# Interactive_SparkFun_Badge.net
KiCad netlist of a schematic drawn in EAGLE
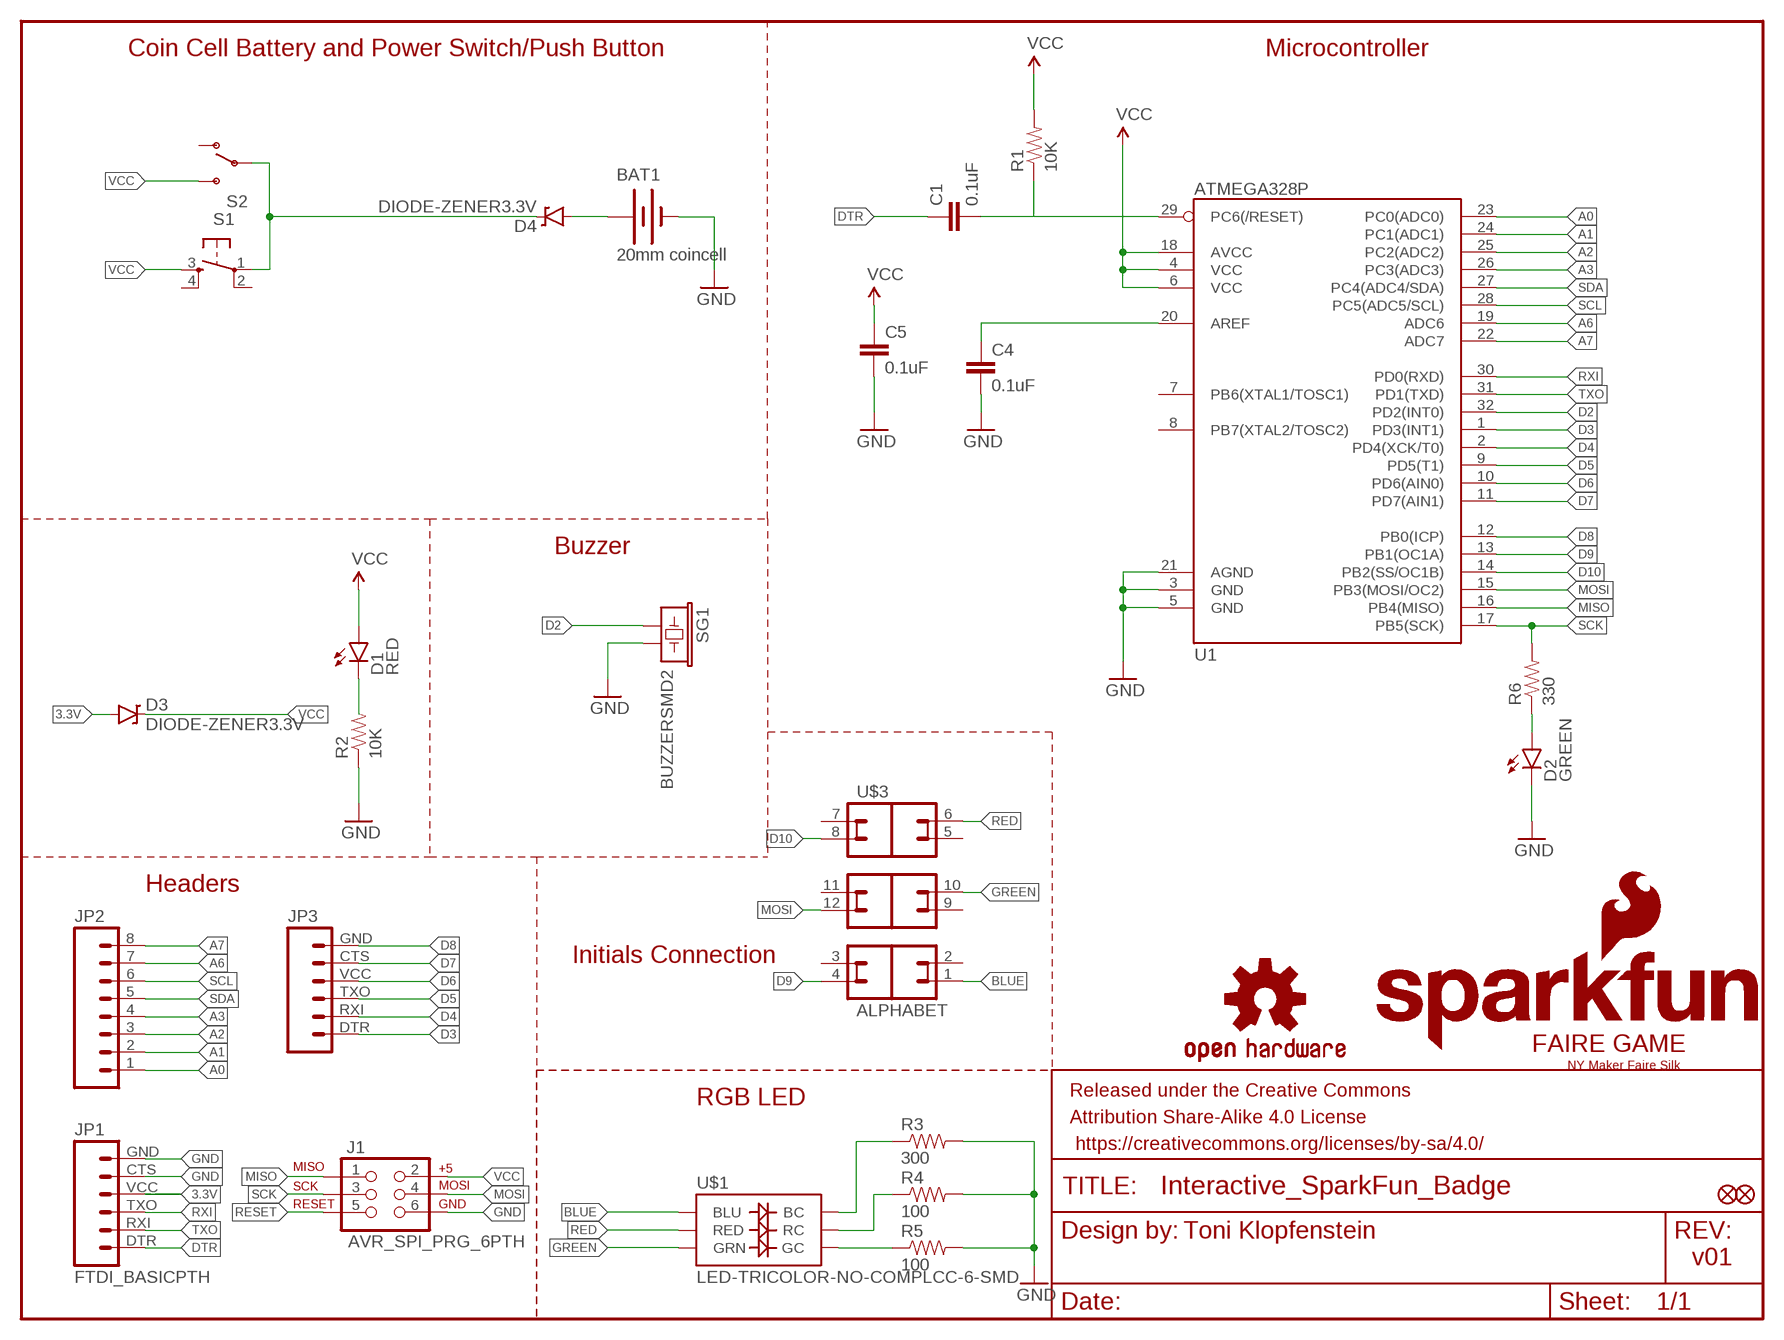
[diagram p0: schematic, sheet 1]

(export (version "E")
  (design (tool "Eeschema 10.0.6"))
  (components
    (comp (ref "BAT1")
      (value "20mm coincell")
      (footprint "eagle-import:BATTCON_20MM_4LEGS")
      (libsource (lib "eagle-import") (part "BATTERY20MM_4LEGS"))
    )
    (comp (ref "C1")
      (value "0.1uF")
      (footprint "eagle-import:0603-CAP")
      (libsource (lib "eagle-import") (part "0.1UF-25V(+80/-20%)(0603)"))
    )
    (comp (ref "C4")
      (value "0.1uF")
      (footprint "eagle-import:0603-CAP")
      (libsource (lib "eagle-import") (part "0.1UF-25V(+80/-20%)(0603)"))
    )
    (comp (ref "C5")
      (value "0.1uF")
      (footprint "eagle-import:0603-CAP")
      (libsource (lib "eagle-import") (part "0.1UF-25V(+80/-20%)(0603)"))
    )
    (comp (ref "D1")
      (value "RED")
      (footprint "eagle-import:LED-0603")
      (libsource (lib "eagle-import") (part "LED-RED0603"))
    )
    (comp (ref "D2")
      (value "GREEN")
      (footprint "eagle-import:LED-0603")
      (libsource (lib "eagle-import") (part "LED-GREEN0603"))
    )
    (comp (ref "D3")
      (value "DIODE-ZENER3.3V")
      (footprint "eagle-import:SOD-323")
      (libsource (lib "eagle-import") (part "DIODE-ZENER3.3V"))
    )
    (comp (ref "D4")
      (value "DIODE-ZENER3.3V")
      (footprint "eagle-import:SOD-323")
      (libsource (lib "eagle-import") (part "DIODE-ZENER3.3V"))
    )
    (comp (ref "FID1")
      (value "FIDUCIAL1X2")
      (footprint "eagle-import:FIDUCIAL-1X2")
      (libsource (lib "eagle-import") (part "FIDUCIAL1X2"))
    )
    (comp (ref "FID2")
      (value "FIDUCIAL1X2")
      (footprint "eagle-import:FIDUCIAL-1X2")
      (libsource (lib "eagle-import") (part "FIDUCIAL1X2"))
    )
    (comp (ref "FRAME1")
      (value "FRAME-LETTER")
      (footprint "eagle-import:CREATIVE_COMMONS")
      (libsource (lib "eagle-import") (part "FRAME-LETTER"))
    )
    (comp (ref "J1")
      (value "AVR_SPI_PRG_6PTH")
      (footprint "eagle-import:2X3")
      (libsource (lib "eagle-import") (part "AVR_SPI_PRG_6PTH"))
    )
    (comp (ref "JP1")
      (value "FTDI_BASICPTH")
      (footprint "eagle-import:FTDI_BASIC")
      (libsource (lib "eagle-import") (part "FTDI_BASICPTH"))
    )
    (comp (ref "JP2")
      (value "M081X08")
      (footprint "eagle-import:1X08")
      (libsource (lib "eagle-import") (part "M081X08"))
    )
    (comp (ref "JP3")
      (value "M06SIP")
      (footprint "eagle-import:1X06")
      (libsource (lib "eagle-import") (part "M06SIP"))
    )
    (comp (ref "LOGO1")
      (value "OSHW-LOGOM")
      (footprint "eagle-import:OSHW-LOGO-M")
      (libsource (lib "eagle-import") (part "OSHW-LOGOM"))
    )
    (comp (ref "R1")
      (value "10K")
      (footprint "eagle-import:0603-RES")
      (libsource (lib "eagle-import") (part "10KOHM1/10W1%(0603)0603"))
    )
    (comp (ref "R2")
      (value "10K")
      (footprint "eagle-import:0603-RES")
      (libsource (lib "eagle-import") (part "10KOHM1/10W1%(0603)0603"))
    )
    (comp (ref "R3")
      (value "300")
      (footprint "eagle-import:0603-RES")
      (libsource (lib "eagle-import") (part "300OHM-1/10W-1%(0603)"))
    )
    (comp (ref "R4")
      (value "100")
      (footprint "eagle-import:0603-RES")
      (libsource (lib "eagle-import") (part "100OHM1/10W1%(0603)"))
    )
    (comp (ref "R5")
      (value "100")
      (footprint "eagle-import:0603-RES")
      (libsource (lib "eagle-import") (part "100OHM1/10W1%(0603)"))
    )
    (comp (ref "R6")
      (value "330")
      (footprint "eagle-import:0603-RES")
      (libsource (lib "eagle-import") (part "330OHM1/10W1%(0603)"))
    )
    (comp (ref "S1")
      (value "TAC_SWITCHSMD")
      (footprint "eagle-import:TACTILE-SWITCH-SMD")
      (libsource (lib "eagle-import") (part "TAC_SWITCHSMD"))
    )
    (comp (ref "S2")
      (value "SWITCH-SPDTSMD")
      (footprint "eagle-import:AYZ0202")
      (libsource (lib "eagle-import") (part "SWITCH-SPDTSMD"))
    )
    (comp (ref "SG1")
      (value "BUZZERSMD2")
      (footprint "eagle-import:BUZZER-CCV")
      (libsource (lib "eagle-import") (part "BUZZERSMD2"))
    )
    (comp (ref "U$1")
      (value "LED-TRICOLOR-NO-COMPLCC-6-SMD")
      (footprint "eagle-import:PLCC-6-LED")
      (libsource (lib "eagle-import") (part "LED-TRICOLOR-NO-COMPLCC-6-SMD"))
    )
    (comp (ref "U$2")
      (value "NY_FAIRE_BACK")
      (footprint "eagle-import:NY_BACK")
      (libsource (lib "eagle-import") (part "NY_FAIRE_BACK"))
    )
    (comp (ref "U$3")
      (value "ALPHABET")
      (footprint "eagle-import:INITIALS")
      (libsource (lib "eagle-import") (part "ALPHABET"))
    )
    (comp (ref "U$4")
      (value "FAIRE_GAME_SILK")
      (footprint "eagle-import:FAIRE_GAME_SILK")
      (libsource (lib "eagle-import") (part "FAIRE_GAME_SILK"))
    )
    (comp (ref "U1")
      (value "ATMEGA328P")
      (footprint "eagle-import:TQFP32-08")
      (libsource (lib "eagle-import") (part "ATMEGA328_SMT"))
    )
  )
  (nets
    (net (code "1") (name "3.3V") (class "Default")
      (node (ref "D3") (pin "A") (pinfunction "A_A") (pintype "passive"))
      (node (ref "JP1") (pin "VCC") (pinfunction "4_VCC") (pintype "passive"))
    )
    (net (code "2") (name "A0") (class "Default")
      (node (ref "JP2") (pin "1") (pinfunction "1_1") (pintype "passive"))
      (node (ref "U1") (pin "23") (pinfunction "PC0(ADC0)_23") (pintype "bidirectional"))
    )
    (net (code "3") (name "A1") (class "Default")
      (node (ref "JP2") (pin "2") (pinfunction "2_2") (pintype "passive"))
      (node (ref "U1") (pin "24") (pinfunction "PC1(ADC1)_24") (pintype "bidirectional"))
    )
    (net (code "4") (name "A2") (class "Default")
      (node (ref "JP2") (pin "3") (pinfunction "3_3") (pintype "passive"))
      (node (ref "U1") (pin "25") (pinfunction "PC2(ADC2)_25") (pintype "bidirectional"))
    )
    (net (code "5") (name "A3") (class "Default")
      (node (ref "JP2") (pin "4") (pinfunction "4_4") (pintype "passive"))
      (node (ref "U1") (pin "26") (pinfunction "PC3(ADC3)_26") (pintype "bidirectional"))
    )
    (net (code "6") (name "A6") (class "Default")
      (node (ref "JP2") (pin "7") (pinfunction "7_7") (pintype "passive"))
      (node (ref "U1") (pin "19") (pinfunction "ADC6_19") (pintype "bidirectional"))
    )
    (net (code "7") (name "A7") (class "Default")
      (node (ref "JP2") (pin "8") (pinfunction "8_8") (pintype "passive"))
      (node (ref "U1") (pin "22") (pinfunction "ADC7_22") (pintype "bidirectional"))
    )
    (net (code "8") (name "BLUE") (class "Default")
      (node (ref "U$1") (pin "AB") (pinfunction "BLU_AB") (pintype "bidirectional"))
      (node (ref "U$3") (pin "1") (pinfunction "1_1") (pintype "passive"))
    )
    (net (code "9") (name "D2") (class "Default")
      (node (ref "SG1") (pin "+") (pinfunction "1_+") (pintype "passive"))
      (node (ref "U1") (pin "32") (pinfunction "PD2(INT0)_32") (pintype "bidirectional"))
    )
    (net (code "10") (name "D3") (class "Default")
      (node (ref "JP3") (pin "DTR") (pinfunction "1_DTR") (pintype "passive"))
      (node (ref "U1") (pin "1") (pinfunction "PD3(INT1)_1") (pintype "bidirectional"))
    )
    (net (code "11") (name "D4") (class "Default")
      (node (ref "JP3") (pin "RXI") (pinfunction "2_RXI") (pintype "passive"))
      (node (ref "U1") (pin "2") (pinfunction "PD4(XCK/T0)_2") (pintype "bidirectional"))
    )
    (net (code "12") (name "D5") (class "Default")
      (node (ref "JP3") (pin "TXO") (pinfunction "3_TXO") (pintype "passive"))
      (node (ref "U1") (pin "9") (pinfunction "PD5(T1)_9") (pintype "bidirectional"))
    )
    (net (code "13") (name "D6") (class "Default")
      (node (ref "JP3") (pin "VCC") (pinfunction "4_VCC") (pintype "passive"))
      (node (ref "U1") (pin "10") (pinfunction "PD6(AIN0)_10") (pintype "bidirectional"))
    )
    (net (code "14") (name "D7") (class "Default")
      (node (ref "JP3") (pin "CTS") (pinfunction "5_CTS") (pintype "passive"))
      (node (ref "U1") (pin "11") (pinfunction "PD7(AIN1)_11") (pintype "bidirectional"))
    )
    (net (code "15") (name "D8") (class "Default")
      (node (ref "JP3") (pin "GND") (pinfunction "6_GND") (pintype "passive"))
      (node (ref "U1") (pin "12") (pinfunction "PB0(ICP)_12") (pintype "bidirectional"))
    )
    (net (code "16") (name "D9") (class "Default")
      (node (ref "U$3") (pin "4") (pinfunction "4_4") (pintype "passive"))
      (node (ref "U1") (pin "13") (pinfunction "PB1(OC1A)_13") (pintype "bidirectional"))
    )
    (net (code "17") (name "D10") (class "Default")
      (node (ref "U$3") (pin "8") (pinfunction "8_8") (pintype "passive"))
      (node (ref "U1") (pin "14") (pinfunction "PB2(SS/OC1B)_14") (pintype "bidirectional"))
    )
    (net (code "18") (name "DTR") (class "Default")
      (node (ref "C1") (pin "1") (pinfunction "1_1") (pintype "passive"))
      (node (ref "JP1") (pin "DTR") (pinfunction "1_DTR") (pintype "passive"))
    )
    (net (code "19") (name "GND") (class "Default")
      (node (ref "BAT1") (pin "2") (pinfunction "-_2") (pintype "power_in"))
      (node (ref "C4") (pin "2") (pinfunction "2_2") (pintype "passive"))
      (node (ref "C5") (pin "2") (pinfunction "2_2") (pintype "passive"))
      (node (ref "D2") (pin "C") (pinfunction "C_C") (pintype "passive"))
      (node (ref "J1") (pin "6") (pinfunction "6_6") (pintype "passive"))
      (node (ref "JP1") (pin "CTS") (pinfunction "5_CTS") (pintype "passive"))
      (node (ref "JP1") (pin "GND") (pinfunction "6_GND") (pintype "passive"))
      (node (ref "R2") (pin "1") (pinfunction "1_1") (pintype "passive"))
      (node (ref "R3") (pin "2") (pinfunction "2_2") (pintype "passive"))
      (node (ref "R4") (pin "2") (pinfunction "2_2") (pintype "passive"))
      (node (ref "R5") (pin "2") (pinfunction "2_2") (pintype "passive"))
      (node (ref "SG1") (pin "-") (pinfunction "2_-") (pintype "passive"))
      (node (ref "U1") (pin "21") (pinfunction "AGND_21") (pintype "bidirectional"))
      (node (ref "U1") (pin "3") (pinfunction "GND_3") (pintype "bidirectional"))
      (node (ref "U1") (pin "5") (pinfunction "GND_5") (pintype "bidirectional"))
    )
    (net (code "20") (name "GREEN") (class "Default")
      (node (ref "U$1") (pin "AG") (pinfunction "GRN_AG") (pintype "bidirectional"))
      (node (ref "U$3") (pin "10") (pinfunction "10_10") (pintype "passive"))
    )
    (net (code "21") (name "MISO") (class "Default")
      (node (ref "J1") (pin "1") (pinfunction "1_1") (pintype "passive"))
      (node (ref "U1") (pin "16") (pinfunction "PB4(MISO)_16") (pintype "bidirectional"))
    )
    (net (code "22") (name "MOSI") (class "Default")
      (node (ref "J1") (pin "4") (pinfunction "4_4") (pintype "passive"))
      (node (ref "U$3") (pin "12") (pinfunction "12_12") (pintype "passive"))
      (node (ref "U1") (pin "15") (pinfunction "PB3(MOSI/OC2)_15") (pintype "bidirectional"))
    )
    (net (code "23") (name "Net-(BAT1-+)") (class "Default")
      (node (ref "BAT1") (pin "1") (pinfunction "+_1") (pintype "power_in"))
      (node (ref "D4") (pin "A") (pinfunction "A_A") (pintype "passive"))
    )
    (net (code "24") (name "Net-(D1-PadC)") (class "Default")
      (node (ref "D1") (pin "C") (pinfunction "C_C") (pintype "passive"))
      (node (ref "R2") (pin "2") (pinfunction "2_2") (pintype "passive"))
    )
    (net (code "25") (name "Net-(D2-PadA)") (class "Default")
      (node (ref "D2") (pin "A") (pinfunction "A_A") (pintype "passive"))
      (node (ref "R6") (pin "1") (pinfunction "1_1") (pintype "passive"))
    )
    (net (code "26") (name "Net-(S2-P)") (class "Default")
      (node (ref "D4") (pin "C") (pinfunction "C_C") (pintype "passive"))
      (node (ref "S1") (pin "1") (pinfunction "1_1") (pintype "passive"))
      (node (ref "S2") (pin "2") (pinfunction "P_2") (pintype "passive"))
    )
    (net (code "27") (name "Net-(U$1-BC)") (class "Default")
      (node (ref "R3") (pin "1") (pinfunction "1_1") (pintype "passive"))
      (node (ref "U$1") (pin "CB") (pinfunction "BC_CB") (pintype "bidirectional"))
    )
    (net (code "28") (name "Net-(U$1-GC)") (class "Default")
      (node (ref "R5") (pin "1") (pinfunction "1_1") (pintype "passive"))
      (node (ref "U$1") (pin "CG") (pinfunction "GC_CG") (pintype "bidirectional"))
    )
    (net (code "29") (name "Net-(U$1-RC)") (class "Default")
      (node (ref "R4") (pin "1") (pinfunction "1_1") (pintype "passive"))
      (node (ref "U$1") (pin "CR") (pinfunction "RC_CR") (pintype "bidirectional"))
    )
    (net (code "30") (name "Net-(U1-AREF)") (class "Default")
      (node (ref "C4") (pin "1") (pinfunction "1_1") (pintype "passive"))
      (node (ref "U1") (pin "20") (pinfunction "AREF_20") (pintype "bidirectional"))
    )
    (net (code "31") (name "RED") (class "Default")
      (node (ref "U$1") (pin "AR") (pinfunction "RED_AR") (pintype "bidirectional"))
      (node (ref "U$3") (pin "6") (pinfunction "6_6") (pintype "passive"))
    )
    (net (code "32") (name "RESET") (class "Default")
      (node (ref "C1") (pin "2") (pinfunction "2_2") (pintype "passive"))
      (node (ref "J1") (pin "5") (pinfunction "5_5") (pintype "passive"))
      (node (ref "R1") (pin "1") (pinfunction "1_1") (pintype "passive"))
      (node (ref "U1") (pin "29") (pinfunction "PC6(/RESET)_29") (pintype "bidirectional"))
    )
    (net (code "33") (name "RXI") (class "Default")
      (node (ref "JP1") (pin "TXO") (pinfunction "3_TXO") (pintype "passive"))
      (node (ref "U1") (pin "30") (pinfunction "PD0(RXD)_30") (pintype "bidirectional"))
    )
    (net (code "34") (name "SCK") (class "Default")
      (node (ref "J1") (pin "3") (pinfunction "3_3") (pintype "passive"))
      (node (ref "R6") (pin "2") (pinfunction "2_2") (pintype "passive"))
      (node (ref "U1") (pin "17") (pinfunction "PB5(SCK)_17") (pintype "bidirectional"))
    )
    (net (code "35") (name "SCL") (class "Default")
      (node (ref "JP2") (pin "6") (pinfunction "6_6") (pintype "passive"))
      (node (ref "U1") (pin "28") (pinfunction "PC5(ADC5/SCL)_28") (pintype "bidirectional"))
    )
    (net (code "36") (name "SDA") (class "Default")
      (node (ref "JP2") (pin "5") (pinfunction "5_5") (pintype "passive"))
      (node (ref "U1") (pin "27") (pinfunction "PC4(ADC4/SDA)_27") (pintype "bidirectional"))
    )
    (net (code "37") (name "TXO") (class "Default")
      (node (ref "JP1") (pin "RXI") (pinfunction "2_RXI") (pintype "passive"))
      (node (ref "U1") (pin "31") (pinfunction "PD1(TXD)_31") (pintype "bidirectional"))
    )
    (net (code "38") (name "VCC") (class "Default")
      (node (ref "C5") (pin "1") (pinfunction "1_1") (pintype "passive"))
      (node (ref "D1") (pin "A") (pinfunction "A_A") (pintype "passive"))
      (node (ref "D3") (pin "C") (pinfunction "C_C") (pintype "passive"))
      (node (ref "J1") (pin "2") (pinfunction "2_2") (pintype "passive"))
      (node (ref "R1") (pin "2") (pinfunction "2_2") (pintype "passive"))
      (node (ref "S1") (pin "3") (pinfunction "3_3") (pintype "passive"))
      (node (ref "S2") (pin "3") (pinfunction "S_3") (pintype "passive"))
      (node (ref "U1") (pin "18") (pinfunction "AVCC_18") (pintype "bidirectional"))
      (node (ref "U1") (pin "4") (pinfunction "VCC_4") (pintype "bidirectional"))
      (node (ref "U1") (pin "6") (pinfunction "VCC_6") (pintype "bidirectional"))
    )
    (net (code "39") (name "unconnected-(S1-Pad2)") (class "Default")
      (node (ref "S1") (pin "2") (pinfunction "2_2") (pintype "passive"))
    )
    (net (code "40") (name "unconnected-(S1-Pad4)") (class "Default")
      (node (ref "S1") (pin "4") (pinfunction "4_4") (pintype "passive"))
    )
    (net (code "41") (name "unconnected-(S2-O-Pad1)") (class "Default")
      (node (ref "S2") (pin "1") (pinfunction "O_1") (pintype "passive"))
    )
    (net (code "42") (name "unconnected-(U$3-Pad2)") (class "Default")
      (node (ref "U$3") (pin "2") (pinfunction "2_2") (pintype "passive"))
    )
    (net (code "43") (name "unconnected-(U$3-Pad3)") (class "Default")
      (node (ref "U$3") (pin "3") (pinfunction "3_3") (pintype "passive"))
    )
    (net (code "44") (name "unconnected-(U$3-Pad5)") (class "Default")
      (node (ref "U$3") (pin "5") (pinfunction "5_5") (pintype "passive"))
    )
    (net (code "45") (name "unconnected-(U$3-Pad7)") (class "Default")
      (node (ref "U$3") (pin "7") (pinfunction "7_7") (pintype "passive"))
    )
    (net (code "46") (name "unconnected-(U$3-Pad9)") (class "Default")
      (node (ref "U$3") (pin "9") (pinfunction "9_9") (pintype "passive"))
    )
    (net (code "47") (name "unconnected-(U$3-Pad11)") (class "Default")
      (node (ref "U$3") (pin "11") (pinfunction "11_11") (pintype "passive"))
    )
    (net (code "48") (name "unconnected-(U1-PB6(XTAL1{slash}TOSC1)-Pad7)") (class "Default")
      (node (ref "U1") (pin "7") (pinfunction "PB6(XTAL1/TOSC1)_7") (pintype "bidirectional"))
    )
    (net (code "49") (name "unconnected-(U1-PB7(XTAL2{slash}TOSC2)-Pad8)") (class "Default")
      (node (ref "U1") (pin "8") (pinfunction "PB7(XTAL2/TOSC2)_8") (pintype "bidirectional"))
    )
  )
)
